# Pre-Avionic-Design.net
KiCad netlist of a schematic drawn in Altium Designer
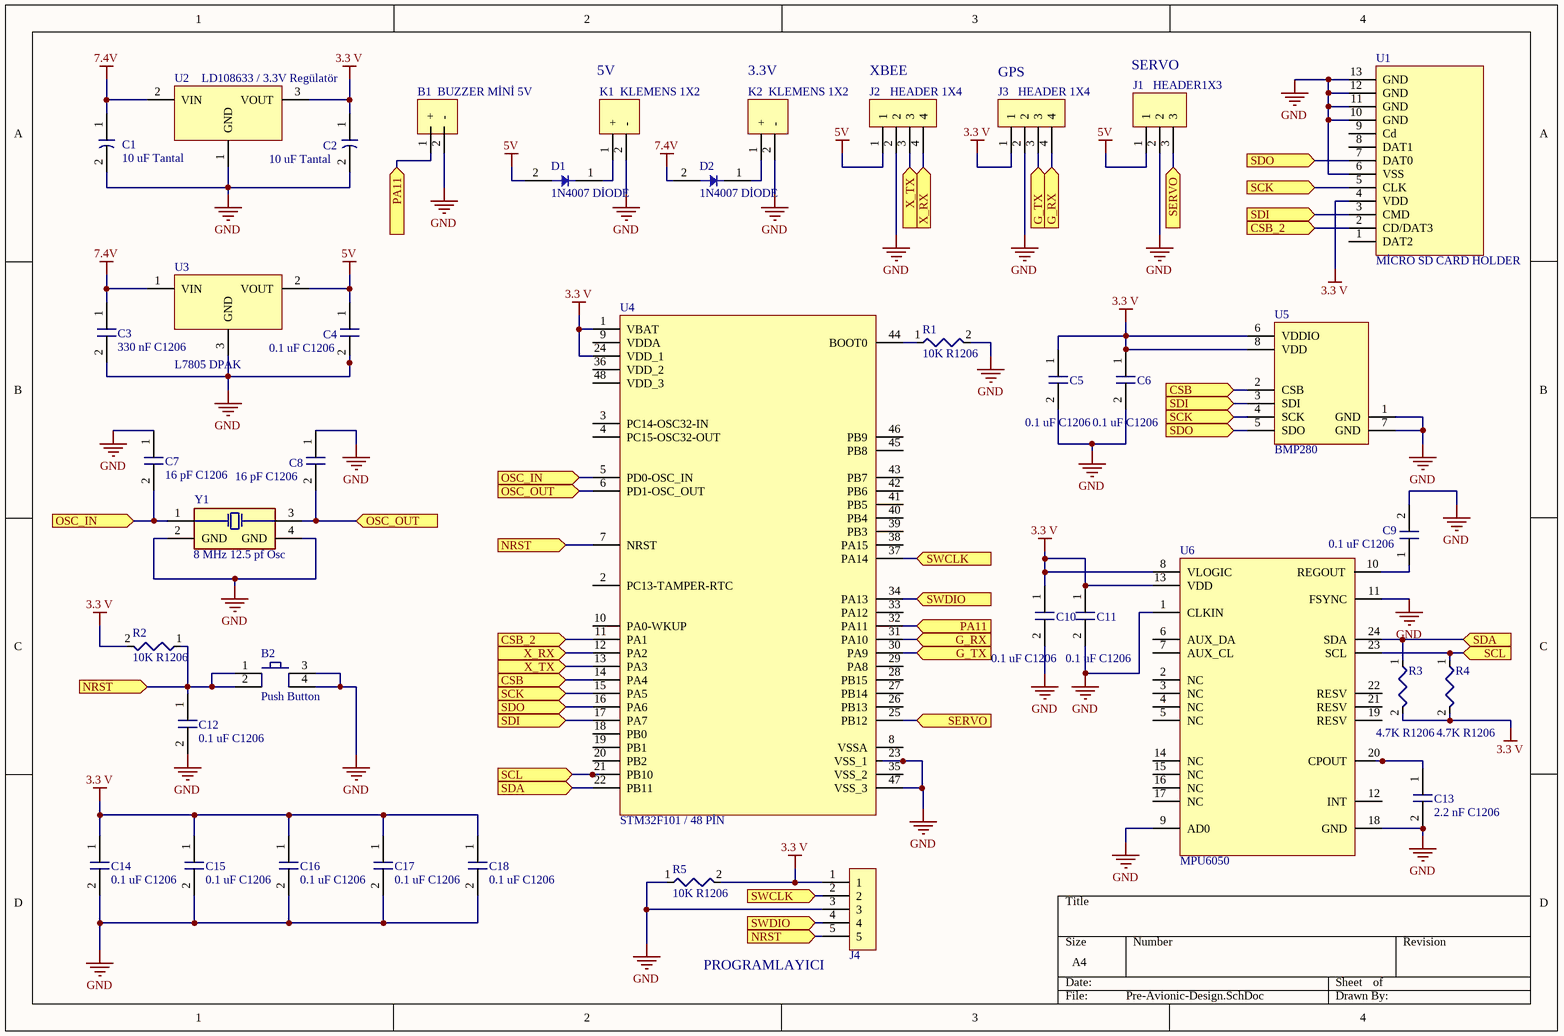
[diagram p0: Pre-Avionic-Design.SchDoc]

(export (version "E")
  (design (tool "Eeschema 10.0.6"))
  (components
    (comp (ref "B1")
      (value "BUZZER MİNİ 5V")
      (footprint "BUZZER MİNİ")
      (description "BUZZER 5V")
      (libsource (lib "Pre-Avonic-Design") (part "BUZZER MİNİ 5V"))
    )
    (comp (ref "B2")
      (value "Push Button")
      (footprint "PUSH_BUTTON")
      (description "SMD Push Button")
      (libsource (lib "Pre-Avonic-Design") (part "Push Button"))
    )
    (comp (ref "C1")
      (value "10 uF Tantal")
      (footprint "C1206-tantal")
      (libsource (lib "Pre-Avonic-Design") (part "10 uF Tantal"))
    )
    (comp (ref "C2")
      (value "10 uF Tantal")
      (footprint "C1206-tantal")
      (libsource (lib "Pre-Avonic-Design") (part "10 uF Tantal"))
    )
    (comp (ref "C3")
      (value "330 nF C1206")
      (footprint "c1206")
      (libsource (lib "Pre-Avonic-Design") (part "330 nF C1206"))
    )
    (comp (ref "C4")
      (value "0.1 uF C1206")
      (footprint "c1206")
      (description "0.1 uF 1206")
      (libsource (lib "Pre-Avonic-Design") (part "0.1 uF C1206"))
    )
    (comp (ref "C5")
      (value "0.1 uF C1206")
      (footprint "c1206")
      (description "0.1 uF 1206")
      (libsource (lib "Pre-Avonic-Design") (part "0.1 uF C1206"))
    )
    (comp (ref "C6")
      (value "0.1 uF C1206")
      (footprint "c1206")
      (description "0.1 uF 1206")
      (libsource (lib "Pre-Avonic-Design") (part "0.1 uF C1206"))
    )
    (comp (ref "C7")
      (value "16 pF C1206")
      (footprint "c1206")
      (libsource (lib "Pre-Avonic-Design") (part "16 pF C1206"))
    )
    (comp (ref "C8")
      (value "16 pF C1206")
      (footprint "c1206")
      (libsource (lib "Pre-Avonic-Design") (part "16 pF C1206"))
    )
    (comp (ref "C9")
      (value "0.1 uF C1206")
      (footprint "c1206")
      (description "0.1 uF 1206")
      (libsource (lib "Pre-Avonic-Design") (part "0.1 uF C1206"))
    )
    (comp (ref "C10")
      (value "0.1 uF C1206")
      (footprint "c1206")
      (description "0.1 uF 1206")
      (libsource (lib "Pre-Avonic-Design") (part "0.1 uF C1206"))
    )
    (comp (ref "C11")
      (value "0.1 uF C1206")
      (footprint "c1206")
      (description "0.1 uF 1206")
      (libsource (lib "Pre-Avonic-Design") (part "0.1 uF C1206"))
    )
    (comp (ref "C12")
      (value "0.1 uF C1206")
      (footprint "c1206")
      (description "0.1 uF 1206")
      (libsource (lib "Pre-Avonic-Design") (part "0.1 uF C1206"))
    )
    (comp (ref "C13")
      (value "2.2 nF C1206")
      (footprint "c1206")
      (libsource (lib "Pre-Avonic-Design") (part "2.2 nF C1206"))
    )
    (comp (ref "C14")
      (value "0.1 uF C1206")
      (footprint "c1206")
      (description "0.1 uF 1206")
      (libsource (lib "Pre-Avonic-Design") (part "0.1 uF C1206"))
    )
    (comp (ref "C15")
      (value "0.1 uF C1206")
      (footprint "c1206")
      (description "0.1 uF 1206")
      (libsource (lib "Pre-Avonic-Design") (part "0.1 uF C1206"))
    )
    (comp (ref "C16")
      (value "0.1 uF C1206")
      (footprint "c1206")
      (description "0.1 uF 1206")
      (libsource (lib "Pre-Avonic-Design") (part "0.1 uF C1206"))
    )
    (comp (ref "C17")
      (value "0.1 uF C1206")
      (footprint "c1206")
      (description "0.1 uF 1206")
      (libsource (lib "Pre-Avonic-Design") (part "0.1 uF C1206"))
    )
    (comp (ref "C18")
      (value "0.1 uF C1206")
      (footprint "c1206")
      (description "0.1 uF 1206")
      (libsource (lib "Pre-Avonic-Design") (part "0.1 uF C1206"))
    )
    (comp (ref "D1")
      (value "1N4007 DİODE")
      (footprint "1N4007")
      (libsource (lib "Pre-Avonic-Design") (part "1N4007 DİODE"))
    )
    (comp (ref "D2")
      (value "1N4007 DİODE")
      (footprint "1N4007")
      (libsource (lib "Pre-Avonic-Design") (part "1N4007 DİODE"))
    )
    (comp (ref "J1")
      (value "HEADER1X3")
      (footprint "HEADER 1X3")
      (description "Header 1x3 2.54mm")
      (libsource (lib "Pre-Avonic-Design") (part "HEADER1X3"))
    )
    (comp (ref "J2")
      (value "HEADER 1X4")
      (footprint "Header 1x4")
      (description "Header1x4 2.54mm")
      (libsource (lib "Pre-Avonic-Design") (part "HEADER 1X4"))
    )
    (comp (ref "J3")
      (value "HEADER 1X4")
      (footprint "Header 1x4")
      (description "Header1x4 2.54mm")
      (libsource (lib "Pre-Avonic-Design") (part "HEADER 1X4"))
    )
    (comp (ref "J4")
      (value "HEADER 1x5")
      (footprint "Header 1x5")
      (description "Header 1x5 2.54mm")
      (libsource (lib "Pre-Avonic-Design") (part "HEADER 1x5"))
    )
    (comp (ref "K1")
      (value "KLEMENS 1X2")
      (footprint "KLEMENS 1X2")
      (description "KLEMANS 1X22 3.6mm")
      (libsource (lib "Pre-Avonic-Design") (part "KLEMENS 1X2"))
    )
    (comp (ref "K2")
      (value "KLEMENS 1X2")
      (footprint "KLEMENS 1X2")
      (description "KLEMANS 1X22 3.6mm")
      (libsource (lib "Pre-Avonic-Design") (part "KLEMENS 1X2"))
    )
    (comp (ref "R1")
      (value "10K R1206")
      (footprint "R1206")
      (libsource (lib "Pre-Avonic-Design") (part "10K R1206"))
    )
    (comp (ref "R2")
      (value "10K R1206")
      (footprint "R1206")
      (libsource (lib "Pre-Avonic-Design") (part "10K R1206"))
    )
    (comp (ref "R3")
      (value "4.7K R1206")
      (footprint "R1206")
      (libsource (lib "Pre-Avonic-Design") (part "4.7K R1206"))
    )
    (comp (ref "R4")
      (value "4.7K R1206")
      (footprint "R1206")
      (libsource (lib "Pre-Avonic-Design") (part "4.7K R1206"))
    )
    (comp (ref "R5")
      (value "10K R1206")
      (footprint "R1206")
      (libsource (lib "Pre-Avonic-Design") (part "10K R1206"))
    )
    (comp (ref "U1")
      (value "MİCRO SD CARD HOLDER")
      (footprint "Micro SD Card Holder")
      (description "MICRO SD CARD HOLDER")
      (libsource (lib "Pre-Avonic-Design") (part "MİCRO SD CARD HOLDER"))
    )
    (comp (ref "U2")
      (value "LD108633 / 3.3V Regülatör")
      (footprint "LD108633 / DPAK - duplicate")
      (description "LD108633 / 3.3 REG")
      (libsource (lib "Pre-Avonic-Design") (part "LD108633"))
    )
    (comp (ref "U3")
      (value "L7805 DPAK")
      (footprint "L7805 / DPAK")
      (description "L7805 / 5V Regülatör")
      (libsource (lib "Pre-Avonic-Design") (part "L7805 DPAK"))
    )
    (comp (ref "U4")
      (value "STM32F101 / 48 PİN")
      (footprint "LQFP48-STM")
      (libsource (lib "Pre-Avonic-Design") (part "STM32F101"))
    )
    (comp (ref "U5")
      (value "BMP280")
      (footprint "BMP280")
      (description "BMP280 SENSOR")
      (libsource (lib "Pre-Avonic-Design") (part "BMP280"))
    )
    (comp (ref "U6")
      (value "MPU6050")
      (footprint "MPU6050 / QFN")
      (description "MPU6050 SENSOR")
      (libsource (lib "Pre-Avonic-Design") (part "MPU6050"))
    )
    (comp (ref "Y1")
      (value "8 MHz 12.5 pf Osc")
      (footprint "8 MHz OSC")
      (libsource (lib "Pre-Avonic-Design") (part "8 MHz 12.5 pf Osc"))
    )
  )
  (nets
    (net (code "1") (name "/CSB") (class "Default")
      (node (ref "U4") (pin "14") (pinfunction "PA4_14") (pintype "passive"))
      (node (ref "U5") (pin "2") (pinfunction "CSB_2") (pintype "passive"))
    )
    (net (code "2") (name "/CSB_2") (class "Default")
      (node (ref "U1") (pin "2") (pinfunction "CD/DAT3_2") (pintype "passive"))
      (node (ref "U4") (pin "11") (pinfunction "PA1_11") (pintype "passive"))
    )
    (net (code "3") (name "/G_RX") (class "Default")
      (node (ref "J3") (pin "4") (pinfunction "4_4") (pintype "passive"))
      (node (ref "U4") (pin "31") (pinfunction "PA10_31") (pintype "passive"))
    )
    (net (code "4") (name "/G_TX") (class "Default")
      (node (ref "J3") (pin "3") (pinfunction "3_3") (pintype "passive"))
      (node (ref "U4") (pin "30") (pinfunction "PA9_30") (pintype "passive"))
    )
    (net (code "5") (name "/NRST") (class "Default")
      (node (ref "B2") (pin "1") (pinfunction "1_1") (pintype "passive"))
      (node (ref "B2") (pin "2") (pinfunction "2_2") (pintype "passive"))
      (node (ref "C12") (pin "1") (pinfunction "1_1") (pintype "passive"))
      (node (ref "J4") (pin "5") (pinfunction "5_5") (pintype "passive"))
      (node (ref "R2") (pin "1") (pinfunction "1_1") (pintype "passive"))
      (node (ref "U4") (pin "7") (pinfunction "NRST_7") (pintype "passive"))
    )
    (net (code "6") (name "/OSC_IN") (class "Default")
      (node (ref "C7") (pin "2") (pinfunction "2_2") (pintype "passive"))
      (node (ref "U4") (pin "5") (pinfunction "PD0-OSC_IN_5") (pintype "passive"))
      (node (ref "Y1") (pin "1") (pinfunction "1_1") (pintype "passive"))
    )
    (net (code "7") (name "/OSC_OUT") (class "Default")
      (node (ref "C8") (pin "2") (pinfunction "2_2") (pintype "passive"))
      (node (ref "U4") (pin "6") (pinfunction "PD1-OSC_OUT_6") (pintype "passive"))
      (node (ref "Y1") (pin "3") (pinfunction "3_3") (pintype "passive"))
    )
    (net (code "8") (name "/PA11") (class "Default")
      (node (ref "B1") (pin "1") (pinfunction "+_1") (pintype "passive"))
      (node (ref "U4") (pin "32") (pinfunction "PA11_32") (pintype "passive"))
    )
    (net (code "9") (name "/SCK") (class "Default")
      (node (ref "U1") (pin "5") (pinfunction "CLK_5") (pintype "passive"))
      (node (ref "U4") (pin "15") (pinfunction "PA5_15") (pintype "passive"))
      (node (ref "U5") (pin "4") (pinfunction "SCK_4") (pintype "passive"))
    )
    (net (code "10") (name "/SCL") (class "Default")
      (node (ref "R4") (pin "1") (pinfunction "1_1") (pintype "passive"))
      (node (ref "U4") (pin "21") (pinfunction "PB10_21") (pintype "passive"))
      (node (ref "U6") (pin "23") (pinfunction "SCL_23") (pintype "passive"))
    )
    (net (code "11") (name "/SDA") (class "Default")
      (node (ref "R3") (pin "1") (pinfunction "1_1") (pintype "passive"))
      (node (ref "U4") (pin "22") (pinfunction "PB11_22") (pintype "passive"))
      (node (ref "U6") (pin "24") (pinfunction "SDA_24") (pintype "passive"))
    )
    (net (code "12") (name "/SDI") (class "Default")
      (node (ref "U1") (pin "3") (pinfunction "CMD_3") (pintype "passive"))
      (node (ref "U4") (pin "17") (pinfunction "PA7_17") (pintype "passive"))
      (node (ref "U5") (pin "3") (pinfunction "SDI_3") (pintype "passive"))
    )
    (net (code "13") (name "/SDO") (class "Default")
      (node (ref "U1") (pin "7") (pinfunction "DAT0_7") (pintype "passive"))
      (node (ref "U4") (pin "16") (pinfunction "PA6_16") (pintype "passive"))
      (node (ref "U5") (pin "5") (pinfunction "SDO_5") (pintype "passive"))
    )
    (net (code "14") (name "/SERVO") (class "Default")
      (node (ref "J1") (pin "3") (pinfunction "3_3") (pintype "passive"))
      (node (ref "U4") (pin "25") (pinfunction "PB12_25") (pintype "passive"))
    )
    (net (code "15") (name "/SWCLK") (class "Default")
      (node (ref "J4") (pin "2") (pinfunction "2_2") (pintype "passive"))
      (node (ref "U4") (pin "37") (pinfunction "PA14_37") (pintype "passive"))
    )
    (net (code "16") (name "/SWDIO") (class "Default")
      (node (ref "J4") (pin "4") (pinfunction "4_4") (pintype "passive"))
      (node (ref "U4") (pin "34") (pinfunction "PA13_34") (pintype "passive"))
    )
    (net (code "17") (name "/X_RX") (class "Default")
      (node (ref "J2") (pin "4") (pinfunction "4_4") (pintype "passive"))
      (node (ref "U4") (pin "12") (pinfunction "PA2_12") (pintype "passive"))
    )
    (net (code "18") (name "/X_TX") (class "Default")
      (node (ref "J2") (pin "3") (pinfunction "3_3") (pintype "passive"))
      (node (ref "U4") (pin "13") (pinfunction "PA3_13") (pintype "passive"))
    )
    (net (code "19") (name "3.3 V") (class "Default")
      (node (ref "C10") (pin "1") (pinfunction "1_1") (pintype "passive"))
      (node (ref "C11") (pin "1") (pinfunction "1_1") (pintype "passive"))
      (node (ref "C14") (pin "1") (pinfunction "1_1") (pintype "passive"))
      (node (ref "C15") (pin "1") (pinfunction "1_1") (pintype "passive"))
      (node (ref "C16") (pin "1") (pinfunction "1_1") (pintype "passive"))
      (node (ref "C17") (pin "1") (pinfunction "1_1") (pintype "passive"))
      (node (ref "C18") (pin "1") (pinfunction "1_1") (pintype "passive"))
      (node (ref "C2") (pin "1") (pinfunction "1_1") (pintype "passive"))
      (node (ref "C5") (pin "1") (pinfunction "1_1") (pintype "passive"))
      (node (ref "C6") (pin "1") (pinfunction "1_1") (pintype "passive"))
      (node (ref "J3") (pin "1") (pinfunction "1_1") (pintype "passive"))
      (node (ref "J4") (pin "1") (pinfunction "1_1") (pintype "passive"))
      (node (ref "R2") (pin "2") (pinfunction "2_2") (pintype "passive"))
      (node (ref "R3") (pin "2") (pinfunction "2_2") (pintype "passive"))
      (node (ref "R4") (pin "2") (pinfunction "2_2") (pintype "passive"))
      (node (ref "R5") (pin "2") (pinfunction "2_2") (pintype "passive"))
      (node (ref "U1") (pin "4") (pinfunction "VDD_4") (pintype "passive"))
      (node (ref "U2") (pin "3") (pinfunction "VOUT_3") (pintype "passive"))
      (node (ref "U4") (pin "1") (pinfunction "VBAT_1") (pintype "passive"))
      (node (ref "U4") (pin "24") (pinfunction "VDD_1_24") (pintype "passive"))
      (node (ref "U5") (pin "6") (pinfunction "VDDIO_6") (pintype "passive"))
      (node (ref "U5") (pin "8") (pinfunction "VDD_8") (pintype "passive"))
      (node (ref "U6") (pin "13") (pinfunction "VDD_13") (pintype "passive"))
      (node (ref "U6") (pin "8") (pinfunction "VLOGIC_8") (pintype "passive"))
    )
    (net (code "20") (name "5V") (class "Default")
      (node (ref "C4") (pin "1") (pinfunction "1_1") (pintype "passive"))
      (node (ref "D1") (pin "2") (pinfunction "2_2") (pintype "passive"))
      (node (ref "J1") (pin "1") (pinfunction "1_1") (pintype "passive"))
      (node (ref "J2") (pin "1") (pinfunction "1_1") (pintype "passive"))
      (node (ref "U3") (pin "2") (pinfunction "VOUT_2") (pintype "passive"))
    )
    (net (code "21") (name "7.4V") (class "Default")
      (node (ref "C1") (pin "1") (pinfunction "1_1") (pintype "passive"))
      (node (ref "C3") (pin "1") (pinfunction "1_1") (pintype "passive"))
      (node (ref "D2") (pin "2") (pinfunction "2_2") (pintype "passive"))
      (node (ref "U2") (pin "2") (pinfunction "VIN_2") (pintype "passive"))
      (node (ref "U3") (pin "1") (pinfunction "VIN_1") (pintype "passive"))
    )
    (net (code "22") (name "GND") (class "Default")
      (node (ref "B1") (pin "2") (pinfunction "-_2") (pintype "passive"))
      (node (ref "B2") (pin "3") (pinfunction "3_3") (pintype "passive"))
      (node (ref "B2") (pin "4") (pinfunction "4_4") (pintype "passive"))
      (node (ref "C1") (pin "2") (pinfunction "2_2") (pintype "passive"))
      (node (ref "C10") (pin "2") (pinfunction "2_2") (pintype "passive"))
      (node (ref "C11") (pin "2") (pinfunction "2_2") (pintype "passive"))
      (node (ref "C12") (pin "2") (pinfunction "2_2") (pintype "passive"))
      (node (ref "C13") (pin "2") (pinfunction "2_2") (pintype "passive"))
      (node (ref "C14") (pin "2") (pinfunction "2_2") (pintype "passive"))
      (node (ref "C15") (pin "2") (pinfunction "2_2") (pintype "passive"))
      (node (ref "C16") (pin "2") (pinfunction "2_2") (pintype "passive"))
      (node (ref "C17") (pin "2") (pinfunction "2_2") (pintype "passive"))
      (node (ref "C18") (pin "2") (pinfunction "2_2") (pintype "passive"))
      (node (ref "C2") (pin "2") (pinfunction "2_2") (pintype "passive"))
      (node (ref "C3") (pin "2") (pinfunction "2_2") (pintype "passive"))
      (node (ref "C4") (pin "2") (pinfunction "2_2") (pintype "passive"))
      (node (ref "C5") (pin "2") (pinfunction "2_2") (pintype "passive"))
      (node (ref "C6") (pin "2") (pinfunction "2_2") (pintype "passive"))
      (node (ref "C7") (pin "1") (pinfunction "1_1") (pintype "passive"))
      (node (ref "C8") (pin "1") (pinfunction "1_1") (pintype "passive"))
      (node (ref "C9") (pin "2") (pinfunction "2_2") (pintype "passive"))
      (node (ref "J1") (pin "2") (pinfunction "2_2") (pintype "passive"))
      (node (ref "J2") (pin "2") (pinfunction "2_2") (pintype "passive"))
      (node (ref "J3") (pin "2") (pinfunction "2_2") (pintype "passive"))
      (node (ref "J4") (pin "3") (pinfunction "3_3") (pintype "passive"))
      (node (ref "K1") (pin "2") (pinfunction "-_2") (pintype "passive"))
      (node (ref "K2") (pin "2") (pinfunction "-_2") (pintype "passive"))
      (node (ref "R1") (pin "2") (pinfunction "2_2") (pintype "passive"))
      (node (ref "R5") (pin "1") (pinfunction "1_1") (pintype "passive"))
      (node (ref "U1") (pin "10") (pinfunction "GND_10") (pintype "passive"))
      (node (ref "U1") (pin "11") (pinfunction "GND_11") (pintype "passive"))
      (node (ref "U1") (pin "12") (pinfunction "GND_12") (pintype "passive"))
      (node (ref "U1") (pin "13") (pinfunction "GND_13") (pintype "passive"))
      (node (ref "U1") (pin "6") (pinfunction "VSS_6") (pintype "passive"))
      (node (ref "U2") (pin "1") (pinfunction "GND_1") (pintype "passive"))
      (node (ref "U3") (pin "3") (pinfunction "GND_3") (pintype "passive"))
      (node (ref "U4") (pin "23") (pinfunction "VSS_1_23") (pintype "passive"))
      (node (ref "U4") (pin "47") (pinfunction "VSS_3_47") (pintype "passive"))
      (node (ref "U5") (pin "1") (pinfunction "GND_1") (pintype "passive"))
      (node (ref "U5") (pin "7") (pinfunction "GND_7") (pintype "passive"))
      (node (ref "U6") (pin "1") (pinfunction "CLKIN_1") (pintype "passive"))
      (node (ref "U6") (pin "11") (pinfunction "FSYNC_11") (pintype "passive"))
      (node (ref "U6") (pin "18") (pinfunction "GND_18") (pintype "passive"))
      (node (ref "U6") (pin "9") (pinfunction "AD0_9") (pintype "passive"))
      (node (ref "Y1") (pin "2") (pinfunction "GND_2") (pintype "passive"))
      (node (ref "Y1") (pin "4") (pinfunction "GND_4") (pintype "passive"))
    )
    (net (code "23") (name "Net-(K1-+)") (class "Default")
      (node (ref "D1") (pin "1") (pinfunction "1_1") (pintype "passive"))
      (node (ref "K1") (pin "1") (pinfunction "+_1") (pintype "passive"))
    )
    (net (code "24") (name "Net-(K2-+)") (class "Default")
      (node (ref "D2") (pin "1") (pinfunction "1_1") (pintype "passive"))
      (node (ref "K2") (pin "1") (pinfunction "+_1") (pintype "passive"))
    )
    (net (code "25") (name "Net-(U4-BOOT0)") (class "Default")
      (node (ref "R1") (pin "1") (pinfunction "1_1") (pintype "passive"))
      (node (ref "U4") (pin "44") (pinfunction "BOOT0_44") (pintype "passive"))
    )
    (net (code "26") (name "Net-(U6-CPOUT)") (class "Default")
      (node (ref "C13") (pin "1") (pinfunction "1_1") (pintype "passive"))
      (node (ref "U6") (pin "20") (pinfunction "CPOUT_20") (pintype "passive"))
    )
    (net (code "27") (name "Net-(U6-REGOUT)") (class "Default")
      (node (ref "C9") (pin "1") (pinfunction "1_1") (pintype "passive"))
      (node (ref "U6") (pin "10") (pinfunction "REGOUT_10") (pintype "passive"))
    )
    (net (code "28") (name "unconnected-(U1-Cd-Pad9)") (class "Default")
      (node (ref "U1") (pin "9") (pinfunction "Cd_9") (pintype "passive"))
    )
    (net (code "29") (name "unconnected-(U1-DAT1-Pad8)") (class "Default")
      (node (ref "U1") (pin "8") (pinfunction "DAT1_8") (pintype "passive"))
    )
    (net (code "30") (name "unconnected-(U1-DAT2-Pad1)") (class "Default")
      (node (ref "U1") (pin "1") (pinfunction "DAT2_1") (pintype "passive"))
    )
    (net (code "31") (name "unconnected-(U4-PA0-WKUP-Pad10)") (class "Default")
      (node (ref "U4") (pin "10") (pinfunction "PA0-WKUP_10") (pintype "passive"))
    )
    (net (code "32") (name "unconnected-(U4-PA8-Pad29)") (class "Default")
      (node (ref "U4") (pin "29") (pinfunction "PA8_29") (pintype "passive"))
    )
    (net (code "33") (name "unconnected-(U4-PA12-Pad33)") (class "Default")
      (node (ref "U4") (pin "33") (pinfunction "PA12_33") (pintype "passive"))
    )
    (net (code "34") (name "unconnected-(U4-PA15-Pad38)") (class "Default")
      (node (ref "U4") (pin "38") (pinfunction "PA15_38") (pintype "passive"))
    )
    (net (code "35") (name "unconnected-(U4-PB0-Pad18)") (class "Default")
      (node (ref "U4") (pin "18") (pinfunction "PB0_18") (pintype "passive"))
    )
    (net (code "36") (name "unconnected-(U4-PB1-Pad19)") (class "Default")
      (node (ref "U4") (pin "19") (pinfunction "PB1_19") (pintype "passive"))
    )
    (net (code "37") (name "unconnected-(U4-PB2-Pad20)") (class "Default")
      (node (ref "U4") (pin "20") (pinfunction "PB2_20") (pintype "passive"))
    )
    (net (code "38") (name "unconnected-(U4-PB3-Pad39)") (class "Default")
      (node (ref "U4") (pin "39") (pinfunction "PB3_39") (pintype "passive"))
    )
    (net (code "39") (name "unconnected-(U4-PB4-Pad40)") (class "Default")
      (node (ref "U4") (pin "40") (pinfunction "PB4_40") (pintype "passive"))
    )
    (net (code "40") (name "unconnected-(U4-PB5-Pad41)") (class "Default")
      (node (ref "U4") (pin "41") (pinfunction "PB5_41") (pintype "passive"))
    )
    (net (code "41") (name "unconnected-(U4-PB6-Pad42)") (class "Default")
      (node (ref "U4") (pin "42") (pinfunction "PB6_42") (pintype "passive"))
    )
    (net (code "42") (name "unconnected-(U4-PB7-Pad43)") (class "Default")
      (node (ref "U4") (pin "43") (pinfunction "PB7_43") (pintype "passive"))
    )
    (net (code "43") (name "unconnected-(U4-PB8-Pad45)") (class "Default")
      (node (ref "U4") (pin "45") (pinfunction "PB8_45") (pintype "passive"))
    )
    (net (code "44") (name "unconnected-(U4-PB9-Pad46)") (class "Default")
      (node (ref "U4") (pin "46") (pinfunction "PB9_46") (pintype "passive"))
    )
    (net (code "45") (name "unconnected-(U4-PB13-Pad26)") (class "Default")
      (node (ref "U4") (pin "26") (pinfunction "PB13_26") (pintype "passive"))
    )
    (net (code "46") (name "unconnected-(U4-PB14-Pad27)") (class "Default")
      (node (ref "U4") (pin "27") (pinfunction "PB14_27") (pintype "passive"))
    )
    (net (code "47") (name "unconnected-(U4-PB15-Pad28)") (class "Default")
      (node (ref "U4") (pin "28") (pinfunction "PB15_28") (pintype "passive"))
    )
    (net (code "48") (name "unconnected-(U4-PC13-TAMPER-RTC-Pad2)") (class "Default")
      (node (ref "U4") (pin "2") (pinfunction "PC13-TAMPER-RTC_2") (pintype "passive"))
    )
    (net (code "49") (name "unconnected-(U4-PC14-OSC32-IN-Pad3)") (class "Default")
      (node (ref "U4") (pin "3") (pinfunction "PC14-OSC32-IN_3") (pintype "passive"))
    )
    (net (code "50") (name "unconnected-(U4-PC15-OSC32-OUT-Pad4)") (class "Default")
      (node (ref "U4") (pin "4") (pinfunction "PC15-OSC32-OUT_4") (pintype "passive"))
    )
    (net (code "51") (name "unconnected-(U4-VDDA-Pad9)") (class "Default")
      (node (ref "U4") (pin "9") (pinfunction "VDDA_9") (pintype "passive"))
    )
    (net (code "52") (name "unconnected-(U4-VDD_2-Pad36)") (class "Default")
      (node (ref "U4") (pin "36") (pinfunction "VDD_2_36") (pintype "passive"))
    )
    (net (code "53") (name "unconnected-(U4-VDD_3-Pad48)") (class "Default")
      (node (ref "U4") (pin "48") (pinfunction "VDD_3_48") (pintype "passive"))
    )
    (net (code "54") (name "unconnected-(U4-VSSA-Pad8)") (class "Default")
      (node (ref "U4") (pin "8") (pinfunction "VSSA_8") (pintype "passive"))
    )
    (net (code "55") (name "unconnected-(U4-VSS_2-Pad35)") (class "Default")
      (node (ref "U4") (pin "35") (pinfunction "VSS_2_35") (pintype "passive"))
    )
    (net (code "56") (name "unconnected-(U6-AUX_CL-Pad7)") (class "Default")
      (node (ref "U6") (pin "7") (pinfunction "AUX_CL_7") (pintype "passive"))
    )
    (net (code "57") (name "unconnected-(U6-AUX_DA-Pad6)") (class "Default")
      (node (ref "U6") (pin "6") (pinfunction "AUX_DA_6") (pintype "passive"))
    )
    (net (code "58") (name "unconnected-(U6-INT-Pad12)") (class "Default")
      (node (ref "U6") (pin "12") (pinfunction "INT_12") (pintype "passive"))
    )
    (net (code "59") (name "unconnected-(U6-NC-Pad2)") (class "Default")
      (node (ref "U6") (pin "2") (pinfunction "NC_2") (pintype "passive"))
    )
    (net (code "60") (name "unconnected-(U6-NC-Pad3)") (class "Default")
      (node (ref "U6") (pin "3") (pinfunction "NC_3") (pintype "passive"))
    )
    (net (code "61") (name "unconnected-(U6-NC-Pad4)") (class "Default")
      (node (ref "U6") (pin "4") (pinfunction "NC_4") (pintype "passive"))
    )
    (net (code "62") (name "unconnected-(U6-NC-Pad5)") (class "Default")
      (node (ref "U6") (pin "5") (pinfunction "NC_5") (pintype "passive"))
    )
    (net (code "63") (name "unconnected-(U6-NC-Pad14)") (class "Default")
      (node (ref "U6") (pin "14") (pinfunction "NC_14") (pintype "passive"))
    )
    (net (code "64") (name "unconnected-(U6-NC-Pad15)") (class "Default")
      (node (ref "U6") (pin "15") (pinfunction "NC_15") (pintype "passive"))
    )
    (net (code "65") (name "unconnected-(U6-NC-Pad16)") (class "Default")
      (node (ref "U6") (pin "16") (pinfunction "NC_16") (pintype "passive"))
    )
    (net (code "66") (name "unconnected-(U6-NC-Pad17)") (class "Default")
      (node (ref "U6") (pin "17") (pinfunction "NC_17") (pintype "passive"))
    )
    (net (code "67") (name "unconnected-(U6-RESV-Pad19)") (class "Default")
      (node (ref "U6") (pin "19") (pinfunction "RESV_19") (pintype "passive"))
    )
    (net (code "68") (name "unconnected-(U6-RESV-Pad21)") (class "Default")
      (node (ref "U6") (pin "21") (pinfunction "RESV_21") (pintype "passive"))
    )
    (net (code "69") (name "unconnected-(U6-RESV-Pad22)") (class "Default")
      (node (ref "U6") (pin "22") (pinfunction "RESV_22") (pintype "passive"))
    )
  )
)
